# Adafruit_MPR_pressure_sensor.net
KiCad netlist of a schematic drawn in EAGLE
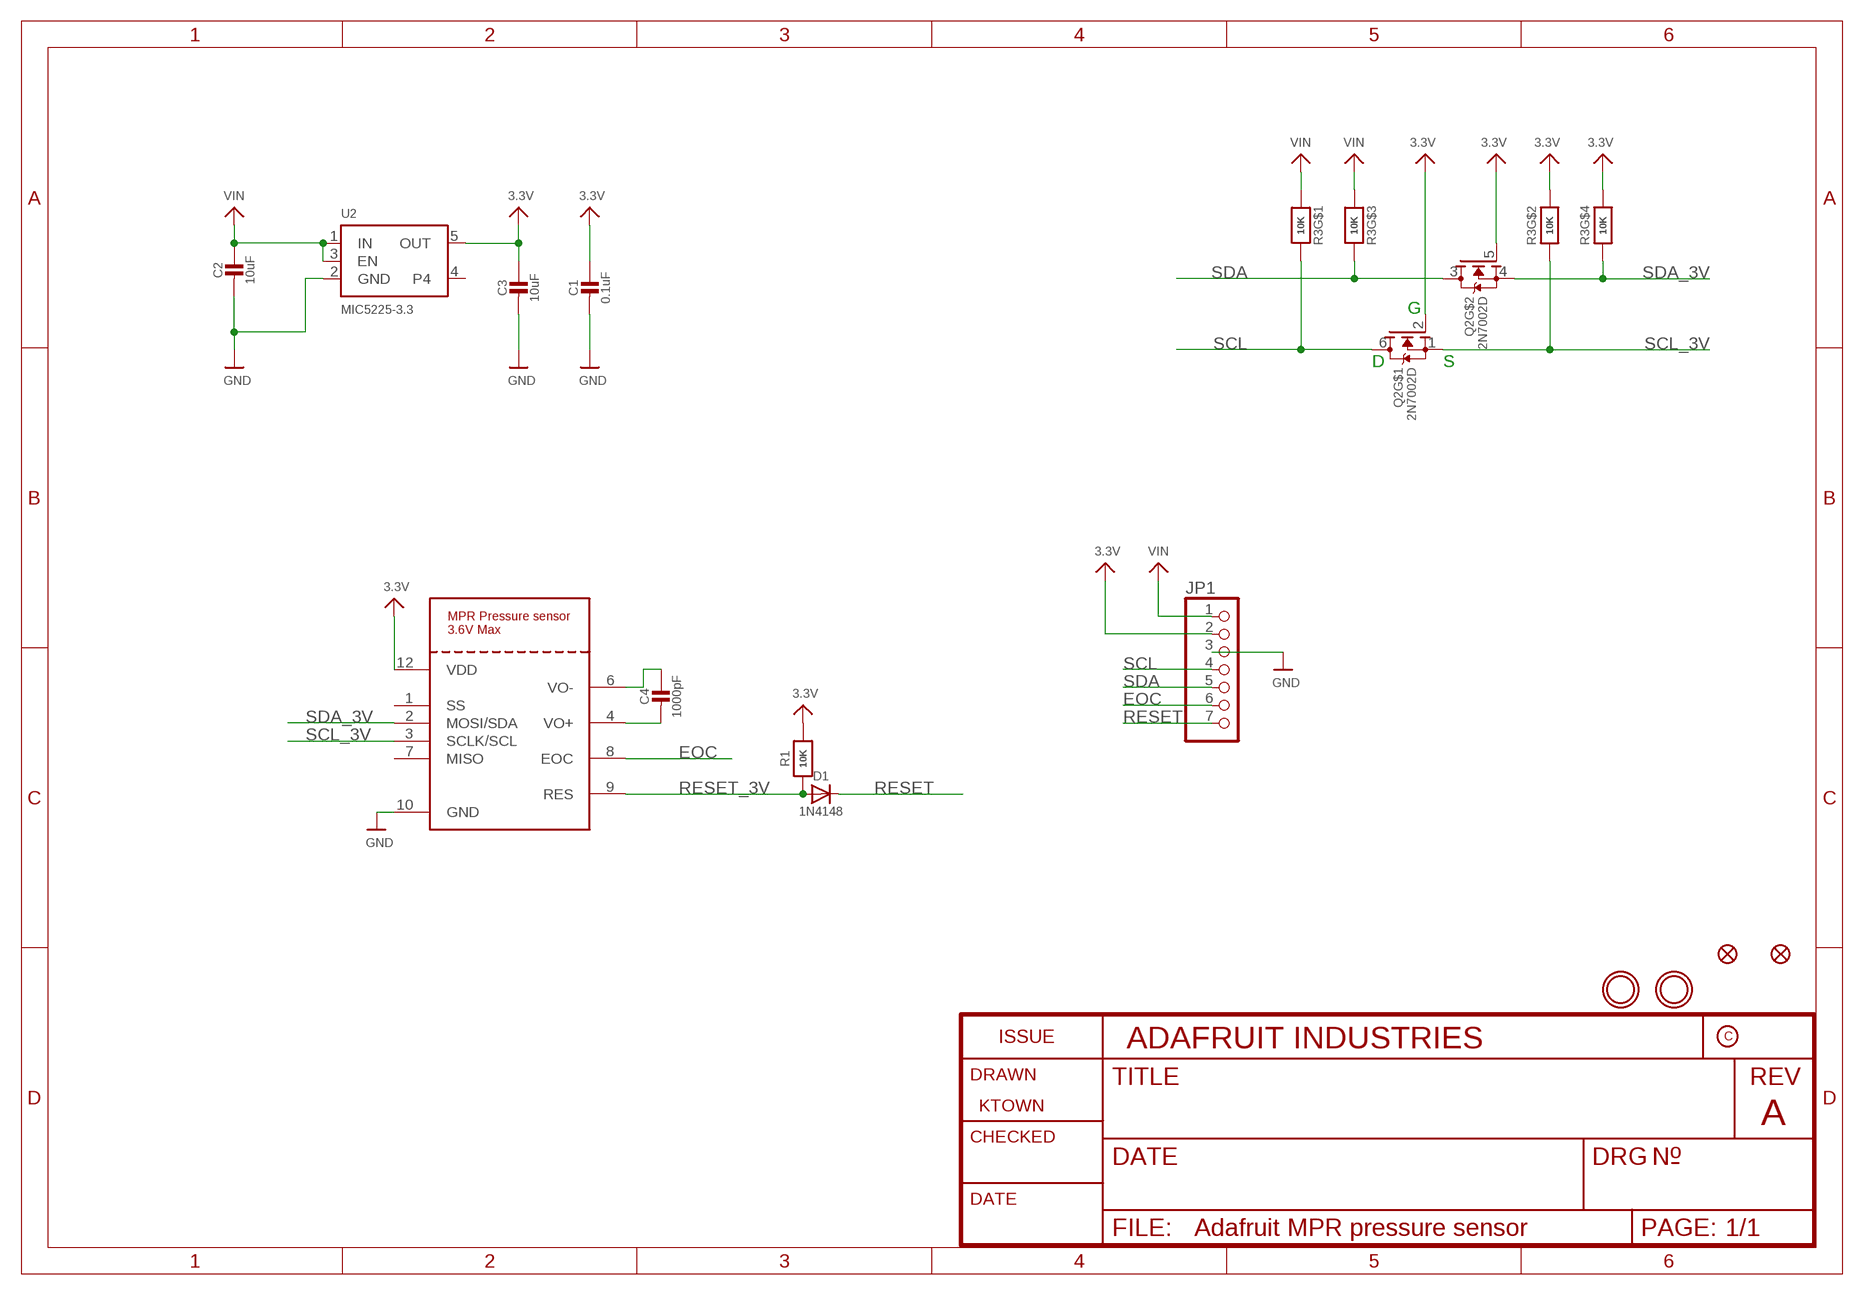
[diagram p0: schematic, sheet 1]

(export (version "E")
  (design (tool "Eeschema 10.0.6"))
  (components
    (comp (ref "C1")
      (value "0.1uF")
      (footprint "eagle-import:0603-NO")
      (libsource (lib "eagle-import") (part "CAP_CERAMIC0603_NO"))
    )
    (comp (ref "C2")
      (value "10uF")
      (footprint "eagle-import:0805-NO")
      (libsource (lib "eagle-import") (part "CAP_CERAMIC0805-NOOUTLINE"))
    )
    (comp (ref "C3")
      (value "10uF")
      (footprint "eagle-import:0805-NO")
      (libsource (lib "eagle-import") (part "CAP_CERAMIC0805-NOOUTLINE"))
    )
    (comp (ref "C4")
      (value "1000pF")
      (footprint "eagle-import:0603-NO")
      (libsource (lib "eagle-import") (part "CAP_CERAMIC0603_NO"))
    )
    (comp (ref "D1")
      (value "1N4148")
      (footprint "eagle-import:SOD-323")
      (libsource (lib "eagle-import") (part "DIODESOD-323"))
    )
    (comp (ref "FID1")
      (value "FIDUCIAL_1MM")
      (footprint "eagle-import:FIDUCIAL_1MM")
      (libsource (lib "eagle-import") (part "FIDUCIAL_1MM"))
    )
    (comp (ref "FID2")
      (value "FIDUCIAL_1MM")
      (footprint "eagle-import:FIDUCIAL_1MM")
      (libsource (lib "eagle-import") (part "FIDUCIAL_1MM"))
    )
    (comp (ref "JP1")
      (value "HEADER-1X770MIL")
      (footprint "eagle-import:1X07_ROUND_70")
      (libsource (lib "eagle-import") (part "HEADER-1X770MIL"))
    )
    (comp (ref "Q2")
      (value "2N7002D")
      (footprint "eagle-import:SOT363")
      (libsource (lib "eagle-import") (part "MOSFET-N_DUAL"))
    )
    (comp (ref "R1")
      (value "10K")
      (footprint "eagle-import:0603-NO")
      (libsource (lib "eagle-import") (part "RESISTOR_0603_NOOUT"))
    )
    (comp (ref "R3")
      (value "10K")
      (footprint "eagle-import:RESPACK_4X0603")
      (libsource (lib "eagle-import") (part "RESISTOR_4PACK"))
    )
    (comp (ref "U$3")
      (value "MOUNTINGHOLE2.5")
      (footprint "eagle-import:MOUNTINGHOLE_2.5_PLATED")
      (libsource (lib "eagle-import") (part "MOUNTINGHOLE2.5"))
    )
    (comp (ref "U$4")
      (value "MOUNTINGHOLE2.5")
      (footprint "eagle-import:MOUNTINGHOLE_2.5_PLATED")
      (libsource (lib "eagle-import") (part "MOUNTINGHOLE2.5"))
    )
    (comp (ref "U$18")
      (value "MPR_SERIES_I2C_PRESSURE")
      (footprint "eagle-import:MPR_SERIES_I2C_PRESSURE")
      (libsource (lib "eagle-import") (part "MPR_SERIES_I2C_PRESSURE"))
    )
    (comp (ref "U2")
      (value "MIC5225-3.3")
      (footprint "eagle-import:SOT23-5")
      (libsource (lib "eagle-import") (part "VREG_SOT23-5"))
    )
  )
  (nets
    (net (code "1") (name "/EOC") (class "Default")
      (node (ref "JP1") (pin "6") (pinfunction "6_6") (pintype "passive"))
      (node (ref "U$18") (pin "8") (pinfunction "EOC_8") (pintype "bidirectional"))
    )
    (net (code "2") (name "/RESET") (class "Default")
      (node (ref "D1") (pin "C") (pinfunction "C_C") (pintype "passive"))
      (node (ref "JP1") (pin "7") (pinfunction "7_7") (pintype "passive"))
    )
    (net (code "3") (name "/RESET_3V") (class "Default")
      (node (ref "D1") (pin "A") (pinfunction "A_A") (pintype "passive"))
      (node (ref "R1") (pin "1") (pinfunction "1_1") (pintype "passive"))
      (node (ref "U$18") (pin "9") (pinfunction "RES_9") (pintype "bidirectional"))
    )
    (net (code "4") (name "/SCL") (class "Default")
      (node (ref "JP1") (pin "4") (pinfunction "4_4") (pintype "passive"))
      (node (ref "Q2") (pin "6") (pinfunction "D_6") (pintype "bidirectional"))
      (node (ref "R3") (pin "8") (pinfunction "2_8") (pintype "passive"))
    )
    (net (code "5") (name "/SCL_3V") (class "Default")
      (node (ref "Q2") (pin "1") (pinfunction "S_1") (pintype "bidirectional"))
      (node (ref "R3") (pin "7") (pinfunction "2_7") (pintype "passive"))
      (node (ref "U$18") (pin "3") (pinfunction "SCLK/SCL_3") (pintype "bidirectional"))
    )
    (net (code "6") (name "/SDA") (class "Default")
      (node (ref "JP1") (pin "5") (pinfunction "5_5") (pintype "passive"))
      (node (ref "Q2") (pin "3") (pinfunction "D_3") (pintype "bidirectional"))
      (node (ref "R3") (pin "6") (pinfunction "2_6") (pintype "passive"))
    )
    (net (code "7") (name "/SDA_3V") (class "Default")
      (node (ref "Q2") (pin "4") (pinfunction "S_4") (pintype "bidirectional"))
      (node (ref "R3") (pin "5") (pinfunction "2_5") (pintype "passive"))
      (node (ref "U$18") (pin "2") (pinfunction "MOSI/SDA_2") (pintype "bidirectional"))
    )
    (net (code "8") (name "3.3V") (class "Default")
      (node (ref "C1") (pin "1") (pinfunction "1_1") (pintype "passive"))
      (node (ref "C3") (pin "1") (pinfunction "1_1") (pintype "passive"))
      (node (ref "JP1") (pin "2") (pinfunction "2_2") (pintype "passive"))
      (node (ref "Q2") (pin "2") (pinfunction "G_2") (pintype "bidirectional"))
      (node (ref "Q2") (pin "5") (pinfunction "G_5") (pintype "bidirectional"))
      (node (ref "R1") (pin "2") (pinfunction "2_2") (pintype "passive"))
      (node (ref "R3") (pin "2") (pinfunction "1_2") (pintype "passive"))
      (node (ref "R3") (pin "4") (pinfunction "1_4") (pintype "passive"))
      (node (ref "U$18") (pin "12") (pinfunction "VDD_12") (pintype "bidirectional"))
      (node (ref "U2") (pin "5") (pinfunction "OUT_5") (pintype "power_in"))
    )
    (net (code "9") (name "GND") (class "Default")
      (node (ref "C1") (pin "2") (pinfunction "2_2") (pintype "passive"))
      (node (ref "C2") (pin "2") (pinfunction "2_2") (pintype "passive"))
      (node (ref "C3") (pin "2") (pinfunction "2_2") (pintype "passive"))
      (node (ref "JP1") (pin "3") (pinfunction "3_3") (pintype "passive"))
      (node (ref "U$18") (pin "10") (pinfunction "GND_10") (pintype "bidirectional"))
      (node (ref "U2") (pin "2") (pinfunction "GND_2") (pintype "power_in"))
    )
    (net (code "10") (name "Net-(U$18-VO+)") (class "Default")
      (node (ref "C4") (pin "2") (pinfunction "2_2") (pintype "passive"))
      (node (ref "U$18") (pin "4") (pinfunction "VO+_4") (pintype "bidirectional"))
    )
    (net (code "11") (name "Net-(U$18-VO-)") (class "Default")
      (node (ref "C4") (pin "1") (pinfunction "1_1") (pintype "passive"))
      (node (ref "U$18") (pin "6") (pinfunction "VO-_6") (pintype "bidirectional"))
    )
    (net (code "12") (name "VIN") (class "Default")
      (node (ref "C2") (pin "1") (pinfunction "1_1") (pintype "passive"))
      (node (ref "JP1") (pin "1") (pinfunction "1_1") (pintype "passive"))
      (node (ref "R3") (pin "1") (pinfunction "1_1") (pintype "passive"))
      (node (ref "R3") (pin "3") (pinfunction "1_3") (pintype "passive"))
      (node (ref "U2") (pin "1") (pinfunction "IN_1") (pintype "power_in"))
      (node (ref "U2") (pin "3") (pinfunction "EN_3") (pintype "input"))
    )
    (net (code "13") (name "unconnected-(U$18-MISO-Pad7)") (class "Default")
      (node (ref "U$18") (pin "7") (pinfunction "MISO_7") (pintype "bidirectional"))
    )
    (net (code "14") (name "unconnected-(U$18-SS-Pad1)") (class "Default")
      (node (ref "U$18") (pin "1") (pinfunction "SS_1") (pintype "bidirectional"))
    )
    (net (code "15") (name "unconnected-(U2-P4-Pad4)") (class "Default")
      (node (ref "U2") (pin "4") (pinfunction "P4_4") (pintype "bidirectional"))
    )
  )
)
